# mic-preamp-mono.net
KiCad netlist of a schematic drawn in EAGLE
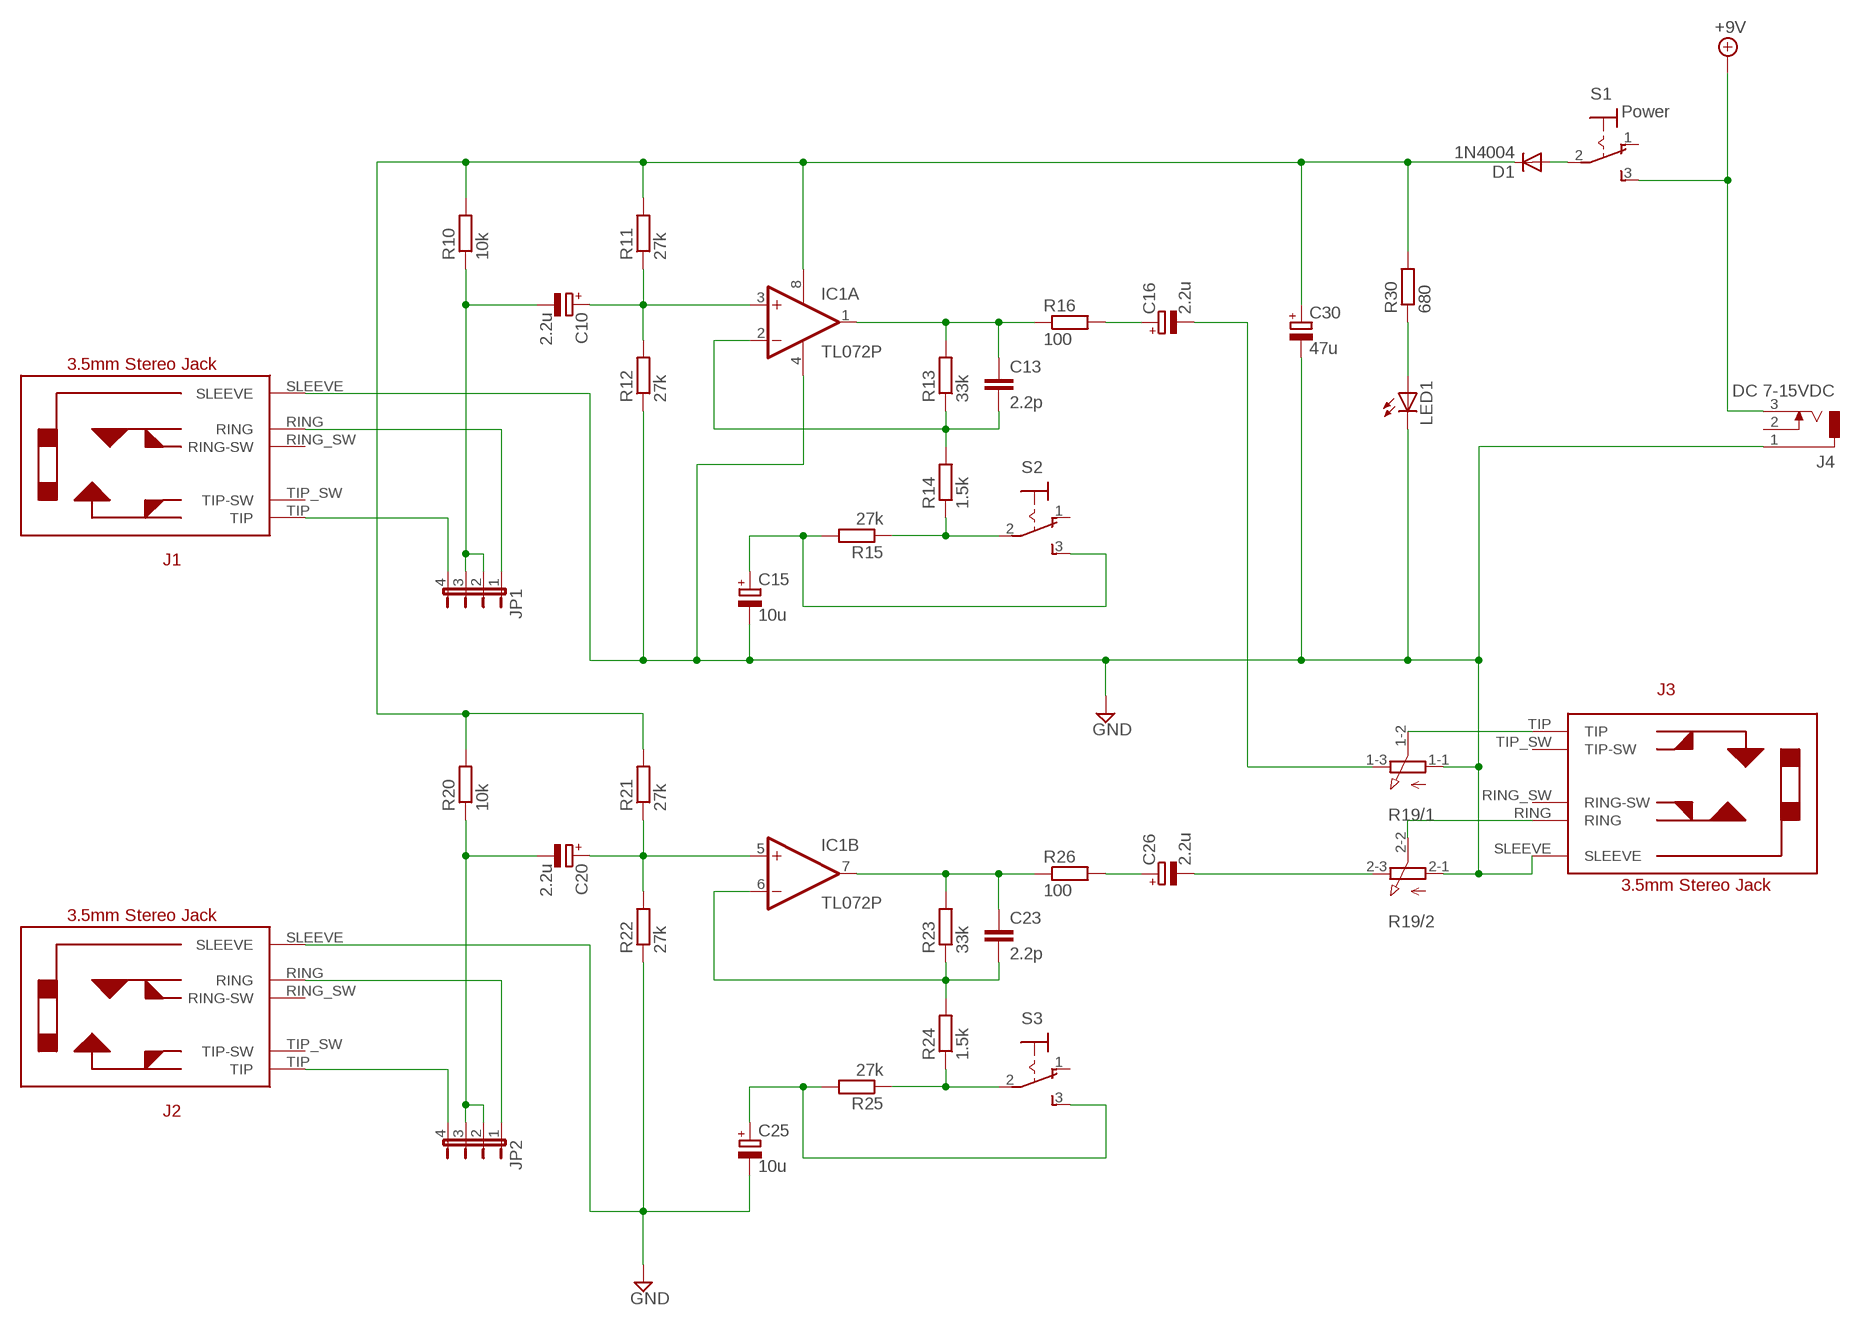
[diagram p0: schematic, sheet 1]

(export (version "E")
  (design (tool "Eeschema 10.0.6"))
  (components
    (comp (ref "C10")
      (value "2.2u")
      (footprint "eagle-import:E2-5")
      (libsource (lib "eagle-import") (part "CPOL-EUE2-5"))
    )
    (comp (ref "C13")
      (value "2.2p")
      (footprint "eagle-import:C025-024X044")
      (libsource (lib "eagle-import") (part "C-EU025-024X044"))
    )
    (comp (ref "C15")
      (value "10u")
      (footprint "eagle-import:E2-5")
      (libsource (lib "eagle-import") (part "CPOL-EUE2-5"))
    )
    (comp (ref "C16")
      (value "2.2u")
      (footprint "eagle-import:E2-5")
      (libsource (lib "eagle-import") (part "CPOL-EUE2-5"))
    )
    (comp (ref "C20")
      (value "2.2u")
      (footprint "eagle-import:E2-5")
      (libsource (lib "eagle-import") (part "CPOL-EUE2-5"))
    )
    (comp (ref "C23")
      (value "2.2p")
      (footprint "eagle-import:C025-024X044")
      (libsource (lib "eagle-import") (part "C-EU025-024X044"))
    )
    (comp (ref "C25")
      (value "10u")
      (footprint "eagle-import:E2-5")
      (libsource (lib "eagle-import") (part "CPOL-EUE2-5"))
    )
    (comp (ref "C26")
      (value "2.2u")
      (footprint "eagle-import:E2-5")
      (libsource (lib "eagle-import") (part "CPOL-EUE2-5"))
    )
    (comp (ref "C30")
      (value "47u")
      (footprint "eagle-import:E2-5")
      (libsource (lib "eagle-import") (part "CPOL-EUE2-5"))
    )
    (comp (ref "D1")
      (value "1N4004")
      (footprint "eagle-import:DO41-10")
      (libsource (lib "eagle-import") (part "1N4004"))
    )
    (comp (ref "IC1")
      (value "TL072P")
      (footprint "eagle-import:DIL08")
      (libsource (lib "eagle-import") (part "TL072P"))
    )
    (comp (ref "J1")
      (value "PICAXE_STEREOJACKSOCKET")
      (footprint "eagle-import:PICAXE_STEREOJACKSOCKET")
      (libsource (lib "eagle-import") (part "PICAXE_STEREOJACKSOCKET"))
    )
    (comp (ref "J2")
      (value "PICAXE_STEREOJACKSOCKET")
      (footprint "eagle-import:PICAXE_STEREOJACKSOCKET")
      (libsource (lib "eagle-import") (part "PICAXE_STEREOJACKSOCKET"))
    )
    (comp (ref "J3")
      (value "Stereo Out")
      (footprint "eagle-import:PICAXE_STEREOJACKSOCKET")
      (libsource (lib "eagle-import") (part "PICAXE_STEREOJACKSOCKET"))
    )
    (comp (ref "J4")
      (value "DC 7-15VDC")
      (footprint "eagle-import:DCJ0202")
      (libsource (lib "eagle-import") (part "DCJ0202"))
    )
    (comp (ref "JP1")
      (value "JP4E")
      (footprint "eagle-import:JP4")
      (libsource (lib "eagle-import") (part "JP4E"))
    )
    (comp (ref "JP2")
      (value "JP4E")
      (footprint "eagle-import:JP4")
      (libsource (lib "eagle-import") (part "JP4E"))
    )
    (comp (ref "LED1")
      (value "LED5MM")
      (footprint "eagle-import:LED5MM")
      (libsource (lib "eagle-import") (part "LED5MM"))
    )
    (comp (ref "R10")
      (value "10k")
      (footprint "eagle-import:0207_5V")
      (libsource (lib "eagle-import") (part "R-EU_0207/5V"))
    )
    (comp (ref "R11")
      (value "27k")
      (footprint "eagle-import:0207_5V")
      (libsource (lib "eagle-import") (part "R-EU_0207/5V"))
    )
    (comp (ref "R12")
      (value "27k")
      (footprint "eagle-import:0207_5V")
      (libsource (lib "eagle-import") (part "R-EU_0207/5V"))
    )
    (comp (ref "R13")
      (value "33k")
      (footprint "eagle-import:0207_5V")
      (libsource (lib "eagle-import") (part "R-EU_0207/5V"))
    )
    (comp (ref "R14")
      (value "1.5k")
      (footprint "eagle-import:0207_5V")
      (libsource (lib "eagle-import") (part "R-EU_0207/5V"))
    )
    (comp (ref "R15")
      (value "27k")
      (footprint "eagle-import:0207_5V")
      (libsource (lib "eagle-import") (part "R-EU_0207/5V"))
    )
    (comp (ref "R16")
      (value "100")
      (footprint "eagle-import:0207_5V")
      (libsource (lib "eagle-import") (part "R-EU_0207/5V"))
    )
    (comp (ref "R19")
      (value "3RP/1610G")
      (footprint "eagle-import:3RP_1610G")
      (libsource (lib "eagle-import") (part "3RP/1610G"))
    )
    (comp (ref "R20")
      (value "10k")
      (footprint "eagle-import:0207_5V")
      (libsource (lib "eagle-import") (part "R-EU_0207/5V"))
    )
    (comp (ref "R21")
      (value "27k")
      (footprint "eagle-import:0207_5V")
      (libsource (lib "eagle-import") (part "R-EU_0207/5V"))
    )
    (comp (ref "R22")
      (value "27k")
      (footprint "eagle-import:0207_5V")
      (libsource (lib "eagle-import") (part "R-EU_0207/5V"))
    )
    (comp (ref "R23")
      (value "33k")
      (footprint "eagle-import:0207_5V")
      (libsource (lib "eagle-import") (part "R-EU_0207/5V"))
    )
    (comp (ref "R24")
      (value "1.5k")
      (footprint "eagle-import:0207_5V")
      (libsource (lib "eagle-import") (part "R-EU_0207/5V"))
    )
    (comp (ref "R25")
      (value "27k")
      (footprint "eagle-import:0207_5V")
      (libsource (lib "eagle-import") (part "R-EU_0207/5V"))
    )
    (comp (ref "R26")
      (value "100")
      (footprint "eagle-import:0207_5V")
      (libsource (lib "eagle-import") (part "R-EU_0207/5V"))
    )
    (comp (ref "R30")
      (value "680")
      (footprint "eagle-import:0207_12")
      (libsource (lib "eagle-import") (part "R-EU_0207/12"))
    )
    (comp (ref "S1")
      (value "Power")
      (footprint "eagle-import:M9040P")
      (libsource (lib "eagle-import") (part "M9040P"))
    )
    (comp (ref "S2")
      (value "M9040P")
      (footprint "eagle-import:M9040P")
      (libsource (lib "eagle-import") (part "M9040P"))
    )
    (comp (ref "S3")
      (value "M9040P")
      (footprint "eagle-import:M9040P")
      (libsource (lib "eagle-import") (part "M9040P"))
    )
  )
  (nets
    (net (code "1") (name "+9V") (class "Default")
      (node (ref "J4") (pin "3") (pinfunction "3_3") (pintype "passive"))
      (node (ref "S1") (pin "3") (pinfunction "S_3") (pintype "passive"))
    )
    (net (code "2") (name "GND") (class "Default")
      (node (ref "C15") (pin "-") (pinfunction "-_-") (pintype "passive"))
      (node (ref "C25") (pin "-") (pinfunction "-_-") (pintype "passive"))
      (node (ref "C30") (pin "-") (pinfunction "-_-") (pintype "passive"))
      (node (ref "IC1") (pin "4") (pinfunction "V-_4") (pintype "power_in"))
      (node (ref "J1") (pin "SLEEVE") (pinfunction "SLEEVE_SLEEVE") (pintype "bidirectional"))
      (node (ref "J2") (pin "SLEEVE") (pinfunction "SLEEVE_SLEEVE") (pintype "bidirectional"))
      (node (ref "J3") (pin "SLEEVE") (pinfunction "SLEEVE_SLEEVE") (pintype "bidirectional"))
      (node (ref "J4") (pin "1") (pinfunction "1_1") (pintype "passive"))
      (node (ref "LED1") (pin "K") (pinfunction "C_K") (pintype "passive"))
      (node (ref "R12") (pin "1") (pinfunction "1_1") (pintype "passive"))
      (node (ref "R19") (pin "1-1") (pinfunction "A_1-1") (pintype "passive"))
      (node (ref "R19") (pin "2-1") (pinfunction "A_2-1") (pintype "passive"))
      (node (ref "R22") (pin "1") (pinfunction "1_1") (pintype "passive"))
    )
    (net (code "3") (name "Net-(C10-Pad-)") (class "Default")
      (node (ref "C10") (pin "-") (pinfunction "-_-") (pintype "passive"))
      (node (ref "JP1") (pin "2") (pinfunction "2_2") (pintype "passive"))
      (node (ref "JP1") (pin "3") (pinfunction "3_3") (pintype "passive"))
      (node (ref "R10") (pin "1") (pinfunction "1_1") (pintype "passive"))
    )
    (net (code "4") (name "Net-(C16-Pad+)") (class "Default")
      (node (ref "C16") (pin "+") (pinfunction "+_+") (pintype "passive"))
      (node (ref "R16") (pin "2") (pinfunction "2_2") (pintype "passive"))
    )
    (net (code "5") (name "Net-(C20-Pad-)") (class "Default")
      (node (ref "C20") (pin "-") (pinfunction "-_-") (pintype "passive"))
      (node (ref "JP2") (pin "2") (pinfunction "2_2") (pintype "passive"))
      (node (ref "JP2") (pin "3") (pinfunction "3_3") (pintype "passive"))
      (node (ref "R20") (pin "1") (pinfunction "1_1") (pintype "passive"))
    )
    (net (code "6") (name "Net-(C26-Pad+)") (class "Default")
      (node (ref "C26") (pin "+") (pinfunction "+_+") (pintype "passive"))
      (node (ref "R26") (pin "2") (pinfunction "2_2") (pintype "passive"))
    )
    (net (code "7") (name "Net-(IC1A-+IN)") (class "Default")
      (node (ref "C10") (pin "+") (pinfunction "+_+") (pintype "passive"))
      (node (ref "IC1") (pin "3") (pinfunction "+IN_3") (pintype "input"))
      (node (ref "R11") (pin "1") (pinfunction "1_1") (pintype "passive"))
      (node (ref "R12") (pin "2") (pinfunction "2_2") (pintype "passive"))
    )
    (net (code "8") (name "Net-(IC1A--IN)") (class "Default")
      (node (ref "C13") (pin "2") (pinfunction "2_2") (pintype "passive"))
      (node (ref "IC1") (pin "2") (pinfunction "-IN_2") (pintype "input"))
      (node (ref "R13") (pin "1") (pinfunction "1_1") (pintype "passive"))
      (node (ref "R14") (pin "2") (pinfunction "2_2") (pintype "passive"))
    )
    (net (code "9") (name "Net-(IC1A-OUT)") (class "Default")
      (node (ref "C13") (pin "1") (pinfunction "1_1") (pintype "passive"))
      (node (ref "IC1") (pin "1") (pinfunction "OUT_1") (pintype "output"))
      (node (ref "R13") (pin "2") (pinfunction "2_2") (pintype "passive"))
      (node (ref "R16") (pin "1") (pinfunction "1_1") (pintype "passive"))
    )
    (net (code "10") (name "Net-(IC1B-+IN)") (class "Default")
      (node (ref "C20") (pin "+") (pinfunction "+_+") (pintype "passive"))
      (node (ref "IC1") (pin "5") (pinfunction "+IN_5") (pintype "input"))
      (node (ref "R21") (pin "1") (pinfunction "1_1") (pintype "passive"))
      (node (ref "R22") (pin "2") (pinfunction "2_2") (pintype "passive"))
    )
    (net (code "11") (name "Net-(IC1B--IN)") (class "Default")
      (node (ref "C23") (pin "2") (pinfunction "2_2") (pintype "passive"))
      (node (ref "IC1") (pin "6") (pinfunction "-IN_6") (pintype "input"))
      (node (ref "R23") (pin "1") (pinfunction "1_1") (pintype "passive"))
      (node (ref "R24") (pin "2") (pinfunction "2_2") (pintype "passive"))
    )
    (net (code "12") (name "Net-(IC1B-OUT)") (class "Default")
      (node (ref "C23") (pin "1") (pinfunction "1_1") (pintype "passive"))
      (node (ref "IC1") (pin "7") (pinfunction "OUT_7") (pintype "output"))
      (node (ref "R23") (pin "2") (pinfunction "2_2") (pintype "passive"))
      (node (ref "R26") (pin "1") (pinfunction "1_1") (pintype "passive"))
    )
    (net (code "13") (name "Net-(IC1C-V+)") (class "Default")
      (node (ref "C30") (pin "+") (pinfunction "+_+") (pintype "passive"))
      (node (ref "D1") (pin "C") (pinfunction "C_C") (pintype "passive"))
      (node (ref "IC1") (pin "8") (pinfunction "V+_8") (pintype "power_in"))
      (node (ref "R10") (pin "2") (pinfunction "2_2") (pintype "passive"))
      (node (ref "R11") (pin "2") (pinfunction "2_2") (pintype "passive"))
      (node (ref "R20") (pin "2") (pinfunction "2_2") (pintype "passive"))
      (node (ref "R21") (pin "2") (pinfunction "2_2") (pintype "passive"))
      (node (ref "R30") (pin "2") (pinfunction "2_2") (pintype "passive"))
    )
    (net (code "14") (name "Net-(J1-PadRING)") (class "Default")
      (node (ref "J1") (pin "RING") (pinfunction "RING_RING") (pintype "bidirectional"))
      (node (ref "JP1") (pin "1") (pinfunction "1_1") (pintype "passive"))
    )
    (net (code "15") (name "Net-(J1-PadTIP)") (class "Default")
      (node (ref "J1") (pin "TIP") (pinfunction "TIP_TIP") (pintype "bidirectional"))
      (node (ref "JP1") (pin "4") (pinfunction "4_4") (pintype "passive"))
    )
    (net (code "16") (name "Net-(J2-PadRING)") (class "Default")
      (node (ref "J2") (pin "RING") (pinfunction "RING_RING") (pintype "bidirectional"))
      (node (ref "JP2") (pin "1") (pinfunction "1_1") (pintype "passive"))
    )
    (net (code "17") (name "Net-(J2-PadTIP)") (class "Default")
      (node (ref "J2") (pin "TIP") (pinfunction "TIP_TIP") (pintype "bidirectional"))
      (node (ref "JP2") (pin "4") (pinfunction "4_4") (pintype "passive"))
    )
    (net (code "18") (name "Net-(LED1-PadA)") (class "Default")
      (node (ref "LED1") (pin "A") (pinfunction "A_A") (pintype "passive"))
      (node (ref "R30") (pin "1") (pinfunction "1_1") (pintype "passive"))
    )
    (net (code "19") (name "Net-(R19A-E)") (class "Default")
      (node (ref "C16") (pin "-") (pinfunction "-_-") (pintype "passive"))
      (node (ref "R19") (pin "1-3") (pinfunction "E_1-3") (pintype "passive"))
    )
    (net (code "20") (name "Net-(R19A-S)") (class "Default")
      (node (ref "J3") (pin "TIP") (pinfunction "TIP_TIP") (pintype "bidirectional"))
      (node (ref "R19") (pin "1-2") (pinfunction "S_1-2") (pintype "passive"))
    )
    (net (code "21") (name "Net-(R19B-E)") (class "Default")
      (node (ref "C26") (pin "-") (pinfunction "-_-") (pintype "passive"))
      (node (ref "R19") (pin "2-3") (pinfunction "E_2-3") (pintype "passive"))
    )
    (net (code "22") (name "Net-(R19B-S)") (class "Default")
      (node (ref "J3") (pin "RING") (pinfunction "RING_RING") (pintype "bidirectional"))
      (node (ref "R19") (pin "2-2") (pinfunction "S_2-2") (pintype "passive"))
    )
    (net (code "23") (name "Net-(S1-P)") (class "Default")
      (node (ref "D1") (pin "A") (pinfunction "A_A") (pintype "passive"))
      (node (ref "S1") (pin "2") (pinfunction "P_2") (pintype "passive"))
    )
    (net (code "24") (name "Net-(S2-P)") (class "Default")
      (node (ref "R14") (pin "1") (pinfunction "1_1") (pintype "passive"))
      (node (ref "R15") (pin "1") (pinfunction "1_1") (pintype "passive"))
      (node (ref "S2") (pin "2") (pinfunction "P_2") (pintype "passive"))
    )
    (net (code "25") (name "Net-(S2-S)") (class "Default")
      (node (ref "C15") (pin "+") (pinfunction "+_+") (pintype "passive"))
      (node (ref "R15") (pin "2") (pinfunction "2_2") (pintype "passive"))
      (node (ref "S2") (pin "3") (pinfunction "S_3") (pintype "passive"))
    )
    (net (code "26") (name "Net-(S3-P)") (class "Default")
      (node (ref "R24") (pin "1") (pinfunction "1_1") (pintype "passive"))
      (node (ref "R25") (pin "1") (pinfunction "1_1") (pintype "passive"))
      (node (ref "S3") (pin "2") (pinfunction "P_2") (pintype "passive"))
    )
    (net (code "27") (name "Net-(S3-S)") (class "Default")
      (node (ref "C25") (pin "+") (pinfunction "+_+") (pintype "passive"))
      (node (ref "R25") (pin "2") (pinfunction "2_2") (pintype "passive"))
      (node (ref "S3") (pin "3") (pinfunction "S_3") (pintype "passive"))
    )
    (net (code "28") (name "unconnected-(J1-RING-SW-PadRING_SW)") (class "Default")
      (node (ref "J1") (pin "RING_SW") (pinfunction "RING-SW_RING_SW") (pintype "bidirectional"))
    )
    (net (code "29") (name "unconnected-(J1-TIP-SW-PadTIP_SW)") (class "Default")
      (node (ref "J1") (pin "TIP_SW") (pinfunction "TIP-SW_TIP_SW") (pintype "bidirectional"))
    )
    (net (code "30") (name "unconnected-(J2-RING-SW-PadRING_SW)") (class "Default")
      (node (ref "J2") (pin "RING_SW") (pinfunction "RING-SW_RING_SW") (pintype "bidirectional"))
    )
    (net (code "31") (name "unconnected-(J2-TIP-SW-PadTIP_SW)") (class "Default")
      (node (ref "J2") (pin "TIP_SW") (pinfunction "TIP-SW_TIP_SW") (pintype "bidirectional"))
    )
    (net (code "32") (name "unconnected-(J3-RING-SW-PadRING_SW)") (class "Default")
      (node (ref "J3") (pin "RING_SW") (pinfunction "RING-SW_RING_SW") (pintype "bidirectional"))
    )
    (net (code "33") (name "unconnected-(J3-TIP-SW-PadTIP_SW)") (class "Default")
      (node (ref "J3") (pin "TIP_SW") (pinfunction "TIP-SW_TIP_SW") (pintype "bidirectional"))
    )
    (net (code "34") (name "unconnected-(J4-Pad2)") (class "Default")
      (node (ref "J4") (pin "2") (pinfunction "2_2") (pintype "passive"))
    )
    (net (code "35") (name "unconnected-(S1-O-Pad1)") (class "Default")
      (node (ref "S1") (pin "1") (pinfunction "O_1") (pintype "passive"))
    )
    (net (code "36") (name "unconnected-(S2-O-Pad1)") (class "Default")
      (node (ref "S2") (pin "1") (pinfunction "O_1") (pintype "passive"))
    )
    (net (code "37") (name "unconnected-(S3-O-Pad1)") (class "Default")
      (node (ref "S3") (pin "1") (pinfunction "O_1") (pintype "passive"))
    )
  )
)
